# untitled.net
KiCad netlist of a schematic drawn in EAGLE
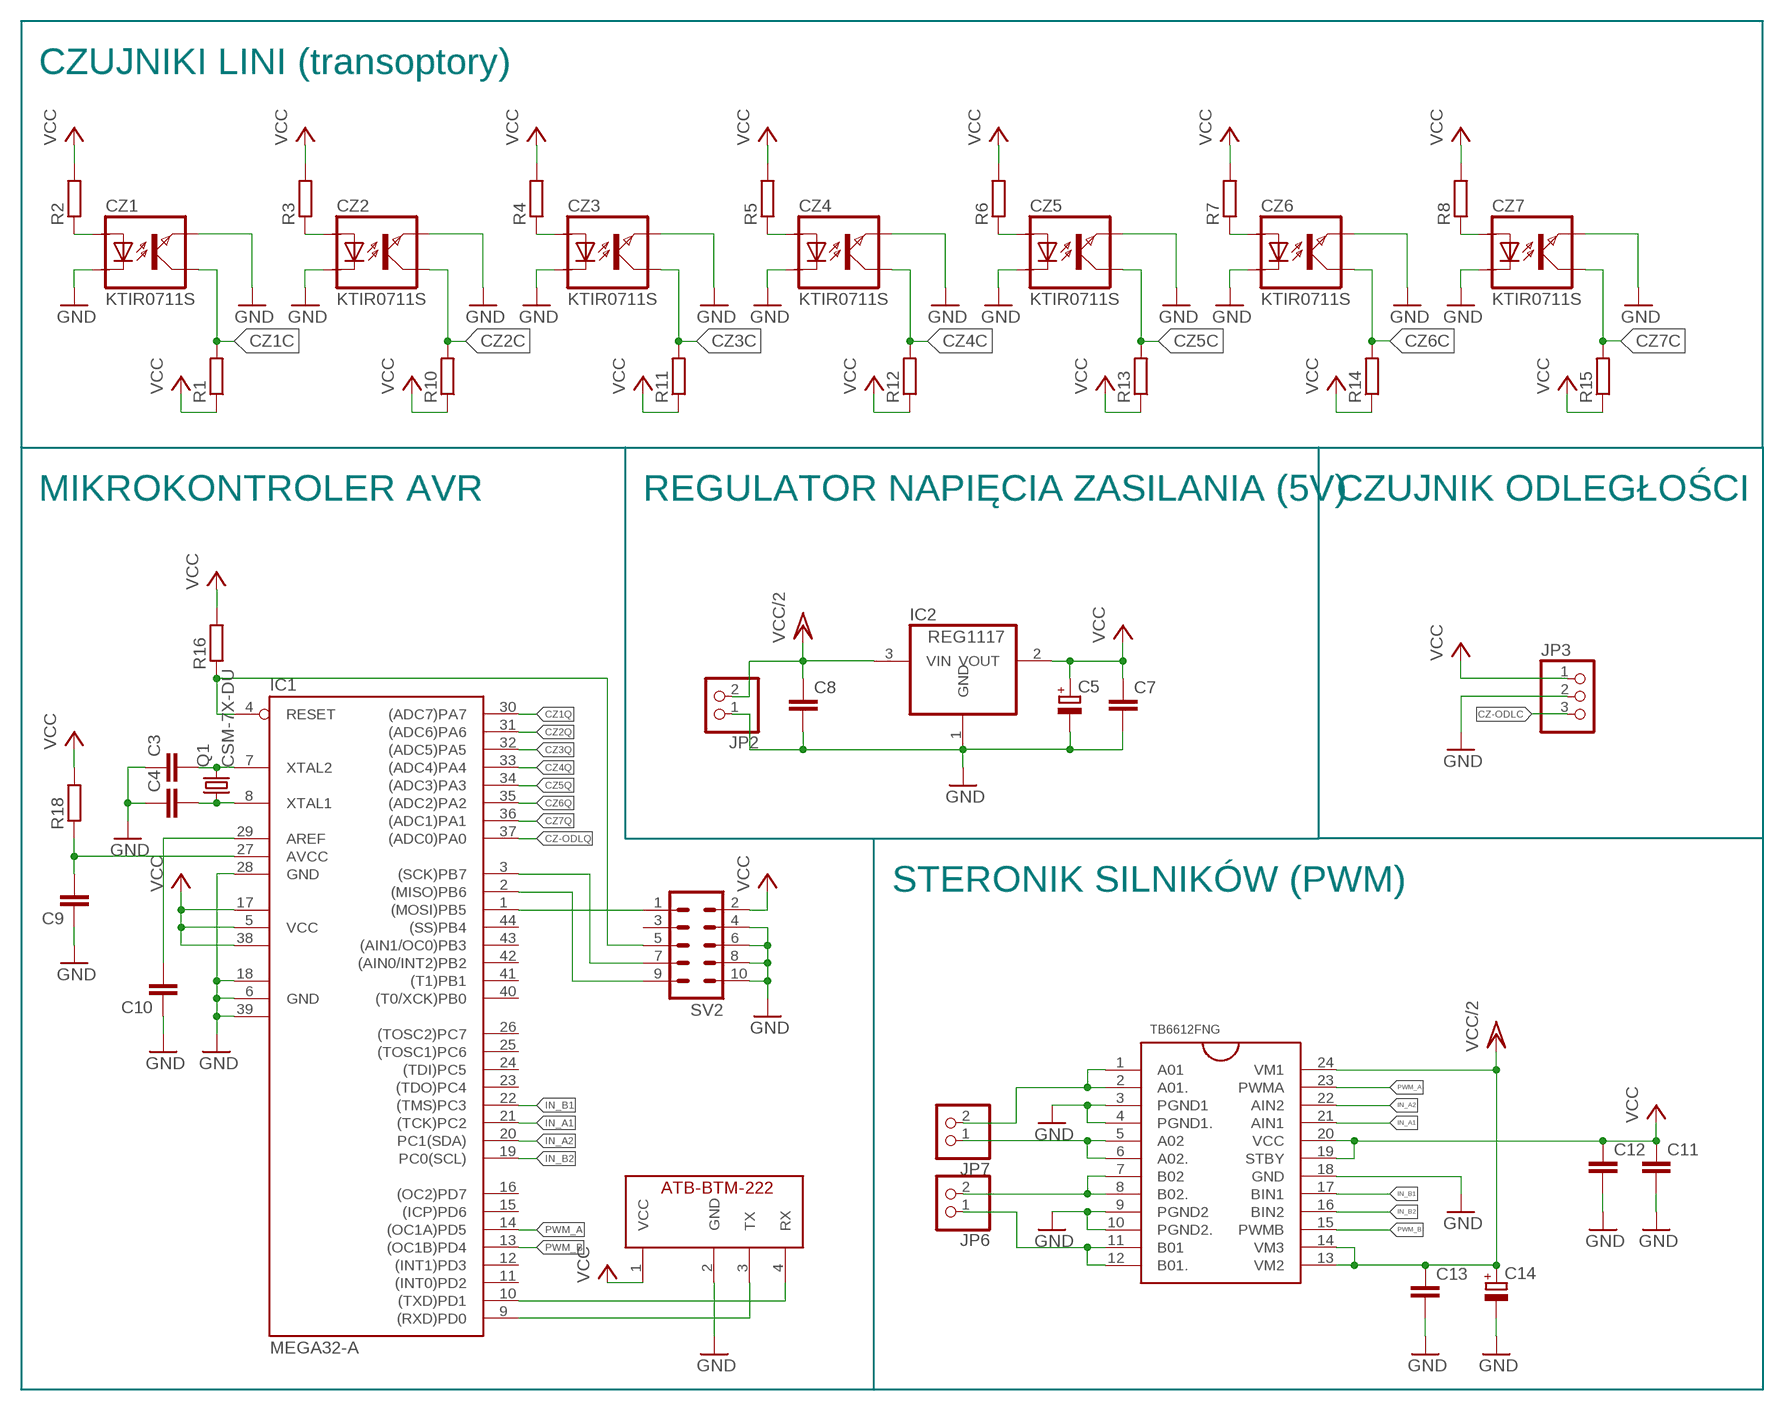
[diagram p0: schematic, sheet 1]

(export (version "E")
  (design (tool "Eeschema 10.0.6"))
  (components
    (comp (ref "C3")
      (value "C-EUC1206K")
      (footprint "eagle-import:C1206K")
      (libsource (lib "eagle-import") (part "C-EUC1206K"))
    )
    (comp (ref "C4")
      (value "C-EUC1206K")
      (footprint "eagle-import:C1206K")
      (libsource (lib "eagle-import") (part "C-EUC1206K"))
    )
    (comp (ref "C5")
      (value "CPOL-EU175TMP-0810")
      (footprint "eagle-import:175TMP-0810")
      (libsource (lib "eagle-import") (part "CPOL-EU175TMP-0810"))
    )
    (comp (ref "C7")
      (value "C-EUC1206K")
      (footprint "eagle-import:C1206K")
      (libsource (lib "eagle-import") (part "C-EUC1206K"))
    )
    (comp (ref "C8")
      (value "C-EUC1206K")
      (footprint "eagle-import:C1206K")
      (libsource (lib "eagle-import") (part "C-EUC1206K"))
    )
    (comp (ref "C9")
      (value "C-EUC1206K")
      (footprint "eagle-import:C1206K")
      (libsource (lib "eagle-import") (part "C-EUC1206K"))
    )
    (comp (ref "C10")
      (value "C-EUC1206K")
      (footprint "eagle-import:C1206K")
      (libsource (lib "eagle-import") (part "C-EUC1206K"))
    )
    (comp (ref "C11")
      (value "C-EUC1206K")
      (footprint "eagle-import:C1206K")
      (libsource (lib "eagle-import") (part "C-EUC1206K"))
    )
    (comp (ref "C12")
      (value "C-EUC1206K")
      (footprint "eagle-import:C1206K")
      (libsource (lib "eagle-import") (part "C-EUC1206K"))
    )
    (comp (ref "C13")
      (value "C-EUC1206K")
      (footprint "eagle-import:C1206K")
      (libsource (lib "eagle-import") (part "C-EUC1206K"))
    )
    (comp (ref "C14")
      (value "CPOL-EU175TMP-0810")
      (footprint "eagle-import:175TMP-0810")
      (libsource (lib "eagle-import") (part "CPOL-EU175TMP-0810"))
    )
    (comp (ref "CZ1")
      (value "KTIR0711S")
      (footprint "eagle-import:TOP")
      (libsource (lib "eagle-import") (part "KTIR0711S"))
    )
    (comp (ref "CZ2")
      (value "KTIR0711S")
      (footprint "eagle-import:TOP")
      (libsource (lib "eagle-import") (part "KTIR0711S"))
    )
    (comp (ref "CZ3")
      (value "KTIR0711S")
      (footprint "eagle-import:TOP")
      (libsource (lib "eagle-import") (part "KTIR0711S"))
    )
    (comp (ref "CZ4")
      (value "KTIR0711S")
      (footprint "eagle-import:TOP")
      (libsource (lib "eagle-import") (part "KTIR0711S"))
    )
    (comp (ref "CZ5")
      (value "KTIR0711S")
      (footprint "eagle-import:TOP")
      (libsource (lib "eagle-import") (part "KTIR0711S"))
    )
    (comp (ref "CZ6")
      (value "KTIR0711S")
      (footprint "eagle-import:TOP")
      (libsource (lib "eagle-import") (part "KTIR0711S"))
    )
    (comp (ref "CZ7")
      (value "KTIR0711S")
      (footprint "eagle-import:TOP")
      (libsource (lib "eagle-import") (part "KTIR0711S"))
    )
    (comp (ref "IC1")
      (value "MEGA32-A")
      (footprint "eagle-import:TQFP44")
      (fields (field (name "MPN") "ATMEGA32-16AU"))
      (libsource (lib "eagle-import") (part "MEGA32-A"))
    )
    (comp (ref "IC2")
      (value "REG1117")
      (footprint "eagle-import:SOT223")
      (libsource (lib "eagle-import") (part "REG1117"))
    )
    (comp (ref "JP2")
      (value "PINHD-1X2")
      (footprint "eagle-import:1X02")
      (libsource (lib "eagle-import") (part "PINHD-1X2"))
    )
    (comp (ref "JP3")
      (value "PINHD-1X3")
      (footprint "eagle-import:1X03")
      (libsource (lib "eagle-import") (part "PINHD-1X3"))
    )
    (comp (ref "JP6")
      (value "PINHD-1X2")
      (footprint "eagle-import:1X02")
      (libsource (lib "eagle-import") (part "PINHD-1X2"))
    )
    (comp (ref "JP7")
      (value "PINHD-1X2")
      (footprint "eagle-import:1X02")
      (libsource (lib "eagle-import") (part "PINHD-1X2"))
    )
    (comp (ref "Q1")
      (value "CSM-7X-DU")
      (footprint "eagle-import:CSM-7X-DU")
      (libsource (lib "eagle-import") (part "CSM-7X-DU"))
    )
    (comp (ref "R1")
      (value "R-EU_R0603")
      (footprint "eagle-import:R0603")
      (libsource (lib "eagle-import") (part "R-EU_R0603"))
    )
    (comp (ref "R2")
      (value "R-EU_R0603")
      (footprint "eagle-import:R0603")
      (libsource (lib "eagle-import") (part "R-EU_R0603"))
    )
    (comp (ref "R3")
      (value "R-EU_R0603")
      (footprint "eagle-import:R0603")
      (libsource (lib "eagle-import") (part "R-EU_R0603"))
    )
    (comp (ref "R4")
      (value "R-EU_R0603")
      (footprint "eagle-import:R0603")
      (libsource (lib "eagle-import") (part "R-EU_R0603"))
    )
    (comp (ref "R5")
      (value "R-EU_R0603")
      (footprint "eagle-import:R0603")
      (libsource (lib "eagle-import") (part "R-EU_R0603"))
    )
    (comp (ref "R6")
      (value "R-EU_R0603")
      (footprint "eagle-import:R0603")
      (libsource (lib "eagle-import") (part "R-EU_R0603"))
    )
    (comp (ref "R7")
      (value "R-EU_R0603")
      (footprint "eagle-import:R0603")
      (libsource (lib "eagle-import") (part "R-EU_R0603"))
    )
    (comp (ref "R8")
      (value "R-EU_R0603")
      (footprint "eagle-import:R0603")
      (libsource (lib "eagle-import") (part "R-EU_R0603"))
    )
    (comp (ref "R10")
      (value "R-EU_R0603")
      (footprint "eagle-import:R0603")
      (libsource (lib "eagle-import") (part "R-EU_R0603"))
    )
    (comp (ref "R11")
      (value "R-EU_R0603")
      (footprint "eagle-import:R0603")
      (libsource (lib "eagle-import") (part "R-EU_R0603"))
    )
    (comp (ref "R12")
      (value "R-EU_R0603")
      (footprint "eagle-import:R0603")
      (libsource (lib "eagle-import") (part "R-EU_R0603"))
    )
    (comp (ref "R13")
      (value "R-EU_R0603")
      (footprint "eagle-import:R0603")
      (libsource (lib "eagle-import") (part "R-EU_R0603"))
    )
    (comp (ref "R14")
      (value "R-EU_R0603")
      (footprint "eagle-import:R0603")
      (libsource (lib "eagle-import") (part "R-EU_R0603"))
    )
    (comp (ref "R15")
      (value "R-EU_R0603")
      (footprint "eagle-import:R0603")
      (libsource (lib "eagle-import") (part "R-EU_R0603"))
    )
    (comp (ref "R16")
      (value "R-EU_R0603")
      (footprint "eagle-import:R0603")
      (libsource (lib "eagle-import") (part "R-EU_R0603"))
    )
    (comp (ref "R18")
      (value "R-EU_R0603")
      (footprint "eagle-import:R0603")
      (libsource (lib "eagle-import") (part "R-EU_R0603"))
    )
    (comp (ref "SV2")
      (value "MA05-2")
      (footprint "eagle-import:MA05-2")
      (libsource (lib "eagle-import") (part "MA05-2"))
    )
    (comp (ref "U$1")
      (value "TB6612FNG")
      (footprint "eagle-import:SSOP24")
      (libsource (lib "eagle-import") (part "TB6612FNG"))
    )
    (comp (ref "U$2")
      (value "ATB-BTM-222")
      (footprint "eagle-import:ATB-BTM-222")
      (libsource (lib "eagle-import") (part "ATB-BTM-222"))
    )
  )
  (nets
    (net (code "1") (name "CZ-ODLC") (class "Default")
      (node (ref "JP3") (pin "3") (pinfunction "3_3") (pintype "passive"))
    )
    (net (code "2") (name "CZ-ODLQ") (class "Default")
      (node (ref "IC1") (pin "37") (pinfunction "(ADC0)PA0_37") (pintype "bidirectional"))
    )
    (net (code "3") (name "CZ1C") (class "Default")
      (node (ref "CZ1") (pin "KOLEKTOR") (pinfunction "KOLEKTOR_KOLEKTOR") (pintype "bidirectional"))
      (node (ref "R1") (pin "2") (pinfunction "2_2") (pintype "passive"))
    )
    (net (code "4") (name "CZ1Q") (class "Default")
      (node (ref "IC1") (pin "30") (pinfunction "(ADC7)PA7_30") (pintype "bidirectional"))
    )
    (net (code "5") (name "CZ2C") (class "Default")
      (node (ref "CZ2") (pin "KOLEKTOR") (pinfunction "KOLEKTOR_KOLEKTOR") (pintype "bidirectional"))
      (node (ref "R10") (pin "2") (pinfunction "2_2") (pintype "passive"))
    )
    (net (code "6") (name "CZ2Q") (class "Default")
      (node (ref "IC1") (pin "31") (pinfunction "(ADC6)PA6_31") (pintype "bidirectional"))
    )
    (net (code "7") (name "CZ3C") (class "Default")
      (node (ref "CZ3") (pin "KOLEKTOR") (pinfunction "KOLEKTOR_KOLEKTOR") (pintype "bidirectional"))
      (node (ref "R11") (pin "2") (pinfunction "2_2") (pintype "passive"))
    )
    (net (code "8") (name "CZ3Q") (class "Default")
      (node (ref "IC1") (pin "32") (pinfunction "(ADC5)PA5_32") (pintype "bidirectional"))
    )
    (net (code "9") (name "CZ4C") (class "Default")
      (node (ref "CZ4") (pin "KOLEKTOR") (pinfunction "KOLEKTOR_KOLEKTOR") (pintype "bidirectional"))
      (node (ref "R12") (pin "2") (pinfunction "2_2") (pintype "passive"))
    )
    (net (code "10") (name "CZ4Q") (class "Default")
      (node (ref "IC1") (pin "33") (pinfunction "(ADC4)PA4_33") (pintype "bidirectional"))
    )
    (net (code "11") (name "CZ5C") (class "Default")
      (node (ref "CZ5") (pin "KOLEKTOR") (pinfunction "KOLEKTOR_KOLEKTOR") (pintype "bidirectional"))
      (node (ref "R13") (pin "2") (pinfunction "2_2") (pintype "passive"))
    )
    (net (code "12") (name "CZ5Q") (class "Default")
      (node (ref "IC1") (pin "34") (pinfunction "(ADC3)PA3_34") (pintype "bidirectional"))
    )
    (net (code "13") (name "CZ6C") (class "Default")
      (node (ref "CZ6") (pin "KOLEKTOR") (pinfunction "KOLEKTOR_KOLEKTOR") (pintype "bidirectional"))
      (node (ref "R14") (pin "2") (pinfunction "2_2") (pintype "passive"))
    )
    (net (code "14") (name "CZ6Q") (class "Default")
      (node (ref "IC1") (pin "35") (pinfunction "(ADC2)PA2_35") (pintype "bidirectional"))
    )
    (net (code "15") (name "CZ7C") (class "Default")
      (node (ref "CZ7") (pin "KOLEKTOR") (pinfunction "KOLEKTOR_KOLEKTOR") (pintype "bidirectional"))
      (node (ref "R15") (pin "2") (pinfunction "2_2") (pintype "passive"))
    )
    (net (code "16") (name "CZ7Q") (class "Default")
      (node (ref "IC1") (pin "36") (pinfunction "(ADC1)PA1_36") (pintype "bidirectional"))
    )
    (net (code "17") (name "GND") (class "Default")
      (node (ref "C10") (pin "1") (pinfunction "1_1") (pintype "passive"))
      (node (ref "C11") (pin "2") (pinfunction "2_2") (pintype "passive"))
      (node (ref "C12") (pin "2") (pinfunction "2_2") (pintype "passive"))
      (node (ref "C13") (pin "2") (pinfunction "2_2") (pintype "passive"))
      (node (ref "C14") (pin "-") (pinfunction "-_-") (pintype "passive"))
      (node (ref "C3") (pin "1") (pinfunction "1_1") (pintype "passive"))
      (node (ref "C4") (pin "1") (pinfunction "1_1") (pintype "passive"))
      (node (ref "C5") (pin "-") (pinfunction "-_-") (pintype "passive"))
      (node (ref "C7") (pin "2") (pinfunction "2_2") (pintype "passive"))
      (node (ref "C8") (pin "2") (pinfunction "2_2") (pintype "passive"))
      (node (ref "C9") (pin "1") (pinfunction "1_1") (pintype "passive"))
      (node (ref "CZ1") (pin "EMITER") (pinfunction "EMITER_EMITER") (pintype "bidirectional"))
      (node (ref "CZ1") (pin "KATODA") (pinfunction "KATODA_KATODA") (pintype "passive"))
      (node (ref "CZ2") (pin "EMITER") (pinfunction "EMITER_EMITER") (pintype "bidirectional"))
      (node (ref "CZ2") (pin "KATODA") (pinfunction "KATODA_KATODA") (pintype "passive"))
      (node (ref "CZ3") (pin "EMITER") (pinfunction "EMITER_EMITER") (pintype "bidirectional"))
      (node (ref "CZ3") (pin "KATODA") (pinfunction "KATODA_KATODA") (pintype "passive"))
      (node (ref "CZ4") (pin "EMITER") (pinfunction "EMITER_EMITER") (pintype "bidirectional"))
      (node (ref "CZ4") (pin "KATODA") (pinfunction "KATODA_KATODA") (pintype "passive"))
      (node (ref "CZ5") (pin "EMITER") (pinfunction "EMITER_EMITER") (pintype "bidirectional"))
      (node (ref "CZ5") (pin "KATODA") (pinfunction "KATODA_KATODA") (pintype "passive"))
      (node (ref "CZ6") (pin "EMITER") (pinfunction "EMITER_EMITER") (pintype "bidirectional"))
      (node (ref "CZ6") (pin "KATODA") (pinfunction "KATODA_KATODA") (pintype "passive"))
      (node (ref "CZ7") (pin "EMITER") (pinfunction "EMITER_EMITER") (pintype "bidirectional"))
      (node (ref "CZ7") (pin "KATODA") (pinfunction "KATODA_KATODA") (pintype "passive"))
      (node (ref "IC1") (pin "18") (pinfunction "GND1_18") (pintype "power_in"))
      (node (ref "IC1") (pin "28") (pinfunction "GND_28") (pintype "power_in"))
      (node (ref "IC1") (pin "39") (pinfunction "GND2_39") (pintype "power_in"))
      (node (ref "IC1") (pin "6") (pinfunction "GND_6") (pintype "power_in"))
      (node (ref "IC2") (pin "1") (pinfunction "GND_1") (pintype "power_in"))
      (node (ref "JP2") (pin "1") (pinfunction "1_1") (pintype "passive"))
      (node (ref "JP3") (pin "2") (pinfunction "2_2") (pintype "passive"))
      (node (ref "SV2") (pin "10") (pinfunction "10_10") (pintype "passive"))
      (node (ref "SV2") (pin "4") (pinfunction "4_4") (pintype "passive"))
      (node (ref "SV2") (pin "6") (pinfunction "6_6") (pintype "passive"))
      (node (ref "SV2") (pin "8") (pinfunction "8_8") (pintype "passive"))
      (node (ref "U$1") (pin "10") (pinfunction "PGND2._10") (pintype "bidirectional"))
      (node (ref "U$1") (pin "18") (pinfunction "GND_18") (pintype "bidirectional"))
      (node (ref "U$1") (pin "3") (pinfunction "PGND1_3") (pintype "bidirectional"))
      (node (ref "U$1") (pin "4") (pinfunction "PGND1._4") (pintype "bidirectional"))
      (node (ref "U$1") (pin "9") (pinfunction "PGND2_9") (pintype "bidirectional"))
      (node (ref "U$2") (pin "2") (pinfunction "GND_2") (pintype "bidirectional"))
    )
    (net (code "18") (name "IN_A1") (class "Default")
      (node (ref "IC1") (pin "21") (pinfunction "(TCK)PC2_21") (pintype "bidirectional"))
      (node (ref "U$1") (pin "21") (pinfunction "AIN1_21") (pintype "bidirectional"))
    )
    (net (code "19") (name "IN_A2") (class "Default")
      (node (ref "IC1") (pin "20") (pinfunction "PC1(SDA)_20") (pintype "bidirectional"))
      (node (ref "U$1") (pin "22") (pinfunction "AIN2_22") (pintype "bidirectional"))
    )
    (net (code "20") (name "IN_B1") (class "Default")
      (node (ref "IC1") (pin "22") (pinfunction "(TMS)PC3_22") (pintype "bidirectional"))
      (node (ref "U$1") (pin "17") (pinfunction "BIN1_17") (pintype "bidirectional"))
    )
    (net (code "21") (name "IN_B2") (class "Default")
      (node (ref "IC1") (pin "19") (pinfunction "PC0(SCL)_19") (pintype "bidirectional"))
      (node (ref "U$1") (pin "16") (pinfunction "BIN2_16") (pintype "bidirectional"))
    )
    (net (code "22") (name "Net-(CZ1-PadANODA)") (class "Default")
      (node (ref "CZ1") (pin "ANODA") (pinfunction "ANODA_ANODA") (pintype "passive"))
      (node (ref "R2") (pin "1") (pinfunction "1_1") (pintype "passive"))
    )
    (net (code "23") (name "Net-(CZ2-PadANODA)") (class "Default")
      (node (ref "CZ2") (pin "ANODA") (pinfunction "ANODA_ANODA") (pintype "passive"))
      (node (ref "R3") (pin "1") (pinfunction "1_1") (pintype "passive"))
    )
    (net (code "24") (name "Net-(CZ3-PadANODA)") (class "Default")
      (node (ref "CZ3") (pin "ANODA") (pinfunction "ANODA_ANODA") (pintype "passive"))
      (node (ref "R4") (pin "1") (pinfunction "1_1") (pintype "passive"))
    )
    (net (code "25") (name "Net-(CZ4-PadANODA)") (class "Default")
      (node (ref "CZ4") (pin "ANODA") (pinfunction "ANODA_ANODA") (pintype "passive"))
      (node (ref "R5") (pin "1") (pinfunction "1_1") (pintype "passive"))
    )
    (net (code "26") (name "Net-(CZ5-PadANODA)") (class "Default")
      (node (ref "CZ5") (pin "ANODA") (pinfunction "ANODA_ANODA") (pintype "passive"))
      (node (ref "R6") (pin "1") (pinfunction "1_1") (pintype "passive"))
    )
    (net (code "27") (name "Net-(CZ6-PadANODA)") (class "Default")
      (node (ref "CZ6") (pin "ANODA") (pinfunction "ANODA_ANODA") (pintype "passive"))
      (node (ref "R7") (pin "1") (pinfunction "1_1") (pintype "passive"))
    )
    (net (code "28") (name "Net-(CZ7-PadANODA)") (class "Default")
      (node (ref "CZ7") (pin "ANODA") (pinfunction "ANODA_ANODA") (pintype "passive"))
      (node (ref "R8") (pin "1") (pinfunction "1_1") (pintype "passive"))
    )
    (net (code "29") (name "Net-(IC1-(MISO)PB6)") (class "Default")
      (node (ref "IC1") (pin "2") (pinfunction "(MISO)PB6_2") (pintype "bidirectional"))
      (node (ref "SV2") (pin "9") (pinfunction "9_9") (pintype "passive"))
    )
    (net (code "30") (name "Net-(IC1-(MOSI)PB5)") (class "Default")
      (node (ref "IC1") (pin "1") (pinfunction "(MOSI)PB5_1") (pintype "bidirectional"))
      (node (ref "SV2") (pin "1") (pinfunction "1_1") (pintype "passive"))
    )
    (net (code "31") (name "Net-(IC1-(RXD)PD0)") (class "Default")
      (node (ref "IC1") (pin "9") (pinfunction "(RXD)PD0_9") (pintype "bidirectional"))
      (node (ref "U$2") (pin "3") (pinfunction "TX_3") (pintype "bidirectional"))
    )
    (net (code "32") (name "Net-(IC1-(SCK)PB7)") (class "Default")
      (node (ref "IC1") (pin "3") (pinfunction "(SCK)PB7_3") (pintype "bidirectional"))
      (node (ref "SV2") (pin "7") (pinfunction "7_7") (pintype "passive"))
    )
    (net (code "33") (name "Net-(IC1-(TXD)PD1)") (class "Default")
      (node (ref "IC1") (pin "10") (pinfunction "(TXD)PD1_10") (pintype "bidirectional"))
      (node (ref "U$2") (pin "4") (pinfunction "RX_4") (pintype "bidirectional"))
    )
    (net (code "34") (name "Net-(IC1-AREF)") (class "Default")
      (node (ref "C10") (pin "2") (pinfunction "2_2") (pintype "passive"))
      (node (ref "IC1") (pin "29") (pinfunction "AREF_29") (pintype "passive"))
    )
    (net (code "35") (name "Net-(IC1-AVCC)") (class "Default")
      (node (ref "C9") (pin "2") (pinfunction "2_2") (pintype "passive"))
      (node (ref "IC1") (pin "27") (pinfunction "AVCC_27") (pintype "power_in"))
      (node (ref "R18") (pin "1") (pinfunction "1_1") (pintype "passive"))
    )
    (net (code "36") (name "Net-(IC1-RESET)") (class "Default")
      (node (ref "IC1") (pin "4") (pinfunction "RESET_4") (pintype "input"))
      (node (ref "R16") (pin "1") (pinfunction "1_1") (pintype "passive"))
      (node (ref "SV2") (pin "5") (pinfunction "5_5") (pintype "passive"))
    )
    (net (code "37") (name "Net-(IC1-XTAL1)") (class "Default")
      (node (ref "C4") (pin "2") (pinfunction "2_2") (pintype "passive"))
      (node (ref "IC1") (pin "8") (pinfunction "XTAL1_8") (pintype "bidirectional"))
      (node (ref "Q1") (pin "1") (pinfunction "1_1") (pintype "passive"))
    )
    (net (code "38") (name "Net-(IC1-XTAL2)") (class "Default")
      (node (ref "C3") (pin "2") (pinfunction "2_2") (pintype "passive"))
      (node (ref "IC1") (pin "7") (pinfunction "XTAL2_7") (pintype "bidirectional"))
      (node (ref "Q1") (pin "2") (pinfunction "2_2") (pintype "passive"))
    )
    (net (code "39") (name "Net-(U$1-A01)") (class "Default")
      (node (ref "JP7") (pin "2") (pinfunction "2_2") (pintype "passive"))
      (node (ref "U$1") (pin "1") (pinfunction "A01_1") (pintype "bidirectional"))
      (node (ref "U$1") (pin "2") (pinfunction "A01._2") (pintype "bidirectional"))
    )
    (net (code "40") (name "Net-(U$1-A02)") (class "Default")
      (node (ref "JP7") (pin "1") (pinfunction "1_1") (pintype "passive"))
      (node (ref "U$1") (pin "5") (pinfunction "A02_5") (pintype "bidirectional"))
      (node (ref "U$1") (pin "6") (pinfunction "A02._6") (pintype "bidirectional"))
    )
    (net (code "41") (name "Net-(U$1-B01)") (class "Default")
      (node (ref "JP6") (pin "1") (pinfunction "1_1") (pintype "passive"))
      (node (ref "U$1") (pin "11") (pinfunction "B01_11") (pintype "bidirectional"))
      (node (ref "U$1") (pin "12") (pinfunction "B01._12") (pintype "bidirectional"))
    )
    (net (code "42") (name "Net-(U$1-B02)") (class "Default")
      (node (ref "JP6") (pin "2") (pinfunction "2_2") (pintype "passive"))
      (node (ref "U$1") (pin "7") (pinfunction "B02_7") (pintype "bidirectional"))
      (node (ref "U$1") (pin "8") (pinfunction "B02._8") (pintype "bidirectional"))
    )
    (net (code "43") (name "PWM_A") (class "Default")
      (node (ref "IC1") (pin "14") (pinfunction "(OC1A)PD5_14") (pintype "bidirectional"))
      (node (ref "U$1") (pin "23") (pinfunction "PWMA_23") (pintype "bidirectional"))
    )
    (net (code "44") (name "PWM_B") (class "Default")
      (node (ref "IC1") (pin "13") (pinfunction "(OC1B)PD4_13") (pintype "bidirectional"))
      (node (ref "U$1") (pin "15") (pinfunction "PWMB_15") (pintype "bidirectional"))
    )
    (net (code "45") (name "VCC") (class "Default")
      (node (ref "C11") (pin "1") (pinfunction "1_1") (pintype "passive"))
      (node (ref "C12") (pin "1") (pinfunction "1_1") (pintype "passive"))
      (node (ref "C5") (pin "+") (pinfunction "+_+") (pintype "passive"))
      (node (ref "C7") (pin "1") (pinfunction "1_1") (pintype "passive"))
      (node (ref "IC1") (pin "17") (pinfunction "VCC1_17") (pintype "power_in"))
      (node (ref "IC1") (pin "38") (pinfunction "VCC2_38") (pintype "power_in"))
      (node (ref "IC1") (pin "5") (pinfunction "VCC_5") (pintype "power_in"))
      (node (ref "IC2") (pin "2") (pinfunction "VOUT_2") (pintype "output"))
      (node (ref "JP3") (pin "1") (pinfunction "1_1") (pintype "passive"))
      (node (ref "R1") (pin "1") (pinfunction "1_1") (pintype "passive"))
      (node (ref "R10") (pin "1") (pinfunction "1_1") (pintype "passive"))
      (node (ref "R11") (pin "1") (pinfunction "1_1") (pintype "passive"))
      (node (ref "R12") (pin "1") (pinfunction "1_1") (pintype "passive"))
      (node (ref "R13") (pin "1") (pinfunction "1_1") (pintype "passive"))
      (node (ref "R14") (pin "1") (pinfunction "1_1") (pintype "passive"))
      (node (ref "R15") (pin "1") (pinfunction "1_1") (pintype "passive"))
      (node (ref "R16") (pin "2") (pinfunction "2_2") (pintype "passive"))
      (node (ref "R18") (pin "2") (pinfunction "2_2") (pintype "passive"))
      (node (ref "R2") (pin "2") (pinfunction "2_2") (pintype "passive"))
      (node (ref "R3") (pin "2") (pinfunction "2_2") (pintype "passive"))
      (node (ref "R4") (pin "2") (pinfunction "2_2") (pintype "passive"))
      (node (ref "R5") (pin "2") (pinfunction "2_2") (pintype "passive"))
      (node (ref "R6") (pin "2") (pinfunction "2_2") (pintype "passive"))
      (node (ref "R7") (pin "2") (pinfunction "2_2") (pintype "passive"))
      (node (ref "R8") (pin "2") (pinfunction "2_2") (pintype "passive"))
      (node (ref "SV2") (pin "2") (pinfunction "2_2") (pintype "passive"))
      (node (ref "U$1") (pin "19") (pinfunction "STBY_19") (pintype "bidirectional"))
      (node (ref "U$1") (pin "20") (pinfunction "VCC_20") (pintype "bidirectional"))
      (node (ref "U$2") (pin "1") (pinfunction "VCC_1") (pintype "bidirectional"))
    )
    (net (code "46") (name "VCC{slash}2") (class "Default")
      (node (ref "C13") (pin "1") (pinfunction "1_1") (pintype "passive"))
      (node (ref "C14") (pin "+") (pinfunction "+_+") (pintype "passive"))
      (node (ref "C8") (pin "1") (pinfunction "1_1") (pintype "passive"))
      (node (ref "IC2") (pin "3") (pinfunction "VIN_3") (pintype "input"))
      (node (ref "JP2") (pin "2") (pinfunction "2_2") (pintype "passive"))
      (node (ref "U$1") (pin "13") (pinfunction "VM2_13") (pintype "bidirectional"))
      (node (ref "U$1") (pin "14") (pinfunction "VM3_14") (pintype "bidirectional"))
      (node (ref "U$1") (pin "24") (pinfunction "VM1_24") (pintype "bidirectional"))
    )
    (net (code "47") (name "unconnected-(IC1-(AIN0{slash}INT2)PB2-Pad42)") (class "Default")
      (node (ref "IC1") (pin "42") (pinfunction "(AIN0/INT2)PB2_42") (pintype "bidirectional"))
    )
    (net (code "48") (name "unconnected-(IC1-(AIN1{slash}OC0)PB3-Pad43)") (class "Default")
      (node (ref "IC1") (pin "43") (pinfunction "(AIN1/OC0)PB3_43") (pintype "bidirectional"))
    )
    (net (code "49") (name "unconnected-(IC1-(ICP)PD6-Pad15)") (class "Default")
      (node (ref "IC1") (pin "15") (pinfunction "(ICP)PD6_15") (pintype "bidirectional"))
    )
    (net (code "50") (name "unconnected-(IC1-(INT0)PD2-Pad11)") (class "Default")
      (node (ref "IC1") (pin "11") (pinfunction "(INT0)PD2_11") (pintype "bidirectional"))
    )
    (net (code "51") (name "unconnected-(IC1-(INT1)PD3-Pad12)") (class "Default")
      (node (ref "IC1") (pin "12") (pinfunction "(INT1)PD3_12") (pintype "bidirectional"))
    )
    (net (code "52") (name "unconnected-(IC1-(OC2)PD7-Pad16)") (class "Default")
      (node (ref "IC1") (pin "16") (pinfunction "(OC2)PD7_16") (pintype "bidirectional"))
    )
    (net (code "53") (name "unconnected-(IC1-(SS)PB4-Pad44)") (class "Default")
      (node (ref "IC1") (pin "44") (pinfunction "(SS)PB4_44") (pintype "bidirectional"))
    )
    (net (code "54") (name "unconnected-(IC1-(T0{slash}XCK)PB0-Pad40)") (class "Default")
      (node (ref "IC1") (pin "40") (pinfunction "(T0/XCK)PB0_40") (pintype "bidirectional"))
    )
    (net (code "55") (name "unconnected-(IC1-(T1)PB1-Pad41)") (class "Default")
      (node (ref "IC1") (pin "41") (pinfunction "(T1)PB1_41") (pintype "bidirectional"))
    )
    (net (code "56") (name "unconnected-(IC1-(TDI)PC5-Pad24)") (class "Default")
      (node (ref "IC1") (pin "24") (pinfunction "(TDI)PC5_24") (pintype "bidirectional"))
    )
    (net (code "57") (name "unconnected-(IC1-(TDO)PC4-Pad23)") (class "Default")
      (node (ref "IC1") (pin "23") (pinfunction "(TDO)PC4_23") (pintype "bidirectional"))
    )
    (net (code "58") (name "unconnected-(IC1-(TOSC1)PC6-Pad25)") (class "Default")
      (node (ref "IC1") (pin "25") (pinfunction "(TOSC1)PC6_25") (pintype "bidirectional"))
    )
    (net (code "59") (name "unconnected-(IC1-(TOSC2)PC7-Pad26)") (class "Default")
      (node (ref "IC1") (pin "26") (pinfunction "(TOSC2)PC7_26") (pintype "bidirectional"))
    )
    (net (code "60") (name "unconnected-(SV2-Pad3)") (class "Default")
      (node (ref "SV2") (pin "3") (pinfunction "3_3") (pintype "passive"))
    )
  )
)
